# 3_3V_BUCK.net
KiCad netlist of a schematic drawn in Altium Designer
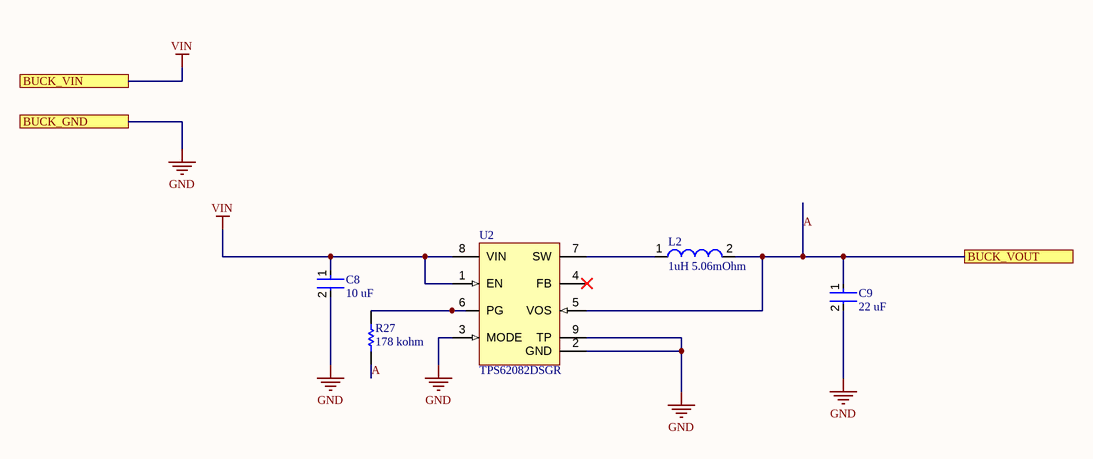
[diagram p0: 3.3V_BUCK.SchDoc]

(export (version "E")
  (design (tool "Eeschema 10.0.6"))
  (components
    (comp (ref "C8")
      (value "10 uF")
      (footprint "FP-GRJ155-0_2-MFG")
      (description "CAP CER 10UF 6.3V X5R 0402")
      (fields (field (name "TOLERANCE") "20%"))
      (libsource (lib "Altium Content Vault") (part "11868f565c42a9108669ba33697ecf6"))
    )
    (comp (ref "C9")
      (value "22 uF")
      (footprint "FP-GRM21B-0_2-e0_2_0_7-IPC_B")
      (description "Chip Multilayer Ceramic Capacitors for General Purpose, 0805, 22uF, X7T, +22%/-33%, 20%, 6.3V")
      (fields (field (name "TOLERANCE") "20%"))
      (libsource (lib "Altium Content Vault") (part "b4654b650e69147ec39a6b967a45e02"))
    )
    (comp (ref "L2")
      (value "1uH 5.06mOhm")
      (footprint "WE-HCI-7040")
      (description "SMD Flat Wire High Current Inductor WE-HCI, L=1.00 µH")
      (libsource (lib "Altium Content Vault") (part "PAS-IND-INDUCTOR-2"))
    )
    (comp (ref "R27")
      (value "178 kohm")
      (footprint "RESC2013X70X40ML20T20")
      (fields (field (name "PART NUMBER") "ERJ-6ENF1783V") (field (name "MANUFACTURER") "Panasonic"))
      (libsource (lib "Altium Content Vault") (part "RES"))
    )
    (comp (ref "U2")
      (value "TPS62082DSGR")
      (footprint "DSG0008A_V")
      (fields (field (name "MANUFACTURER") "Texas Instruments"))
      (libsource (lib "Altium Content Vault") (part "TI-TPS62082DSG8-1600X900TP"))
    )
  )
  (nets
    (net (code "1") (name "/A") (class "Default")
      (node (ref "C9") (pin "1") (pinfunction "1_1") (pintype "passive"))
      (node (ref "L2") (pin "2") (pinfunction "2_2") (pintype "passive"))
      (node (ref "R27") (pin "1") (pinfunction "1_1") (pintype "passive"))
      (node (ref "U2") (pin "5") (pinfunction "VOS_5") (pintype "input"))
    )
    (net (code "2") (name "GND") (class "Default")
      (node (ref "C8") (pin "2") (pinfunction "2_2") (pintype "passive"))
      (node (ref "C9") (pin "2") (pinfunction "2_2") (pintype "passive"))
      (node (ref "U2") (pin "2") (pinfunction "GND_2") (pintype "power_in"))
      (node (ref "U2") (pin "3") (pinfunction "MODE_3") (pintype "input"))
      (node (ref "U2") (pin "9") (pinfunction "TP_9") (pintype "power_in"))
    )
    (net (code "3") (name "Net-(U2-PG)") (class "Default")
      (node (ref "R27") (pin "2") (pinfunction "2_2") (pintype "passive"))
      (node (ref "U2") (pin "6") (pinfunction "PG_6") (pintype "tri_state"))
    )
    (net (code "4") (name "Net-(U2-SW)") (class "Default")
      (node (ref "L2") (pin "1") (pinfunction "1_1") (pintype "passive"))
      (node (ref "U2") (pin "7") (pinfunction "SW_7") (pintype "power_in"))
    )
    (net (code "5") (name "VIN") (class "Default")
      (node (ref "C8") (pin "1") (pinfunction "1_1") (pintype "passive"))
      (node (ref "U2") (pin "1") (pinfunction "EN_1") (pintype "input"))
      (node (ref "U2") (pin "8") (pinfunction "VIN_8") (pintype "power_in"))
    )
    (net (code "6") (name "unconnected-(U2-FB-Pad4)") (class "Default")
      (node (ref "U2") (pin "4") (pinfunction "FB_4") (pintype "passive+no_connect"))
    )
  )
)
